# TPS60400.net
KiCad netlist of a schematic drawn in Altium Designer
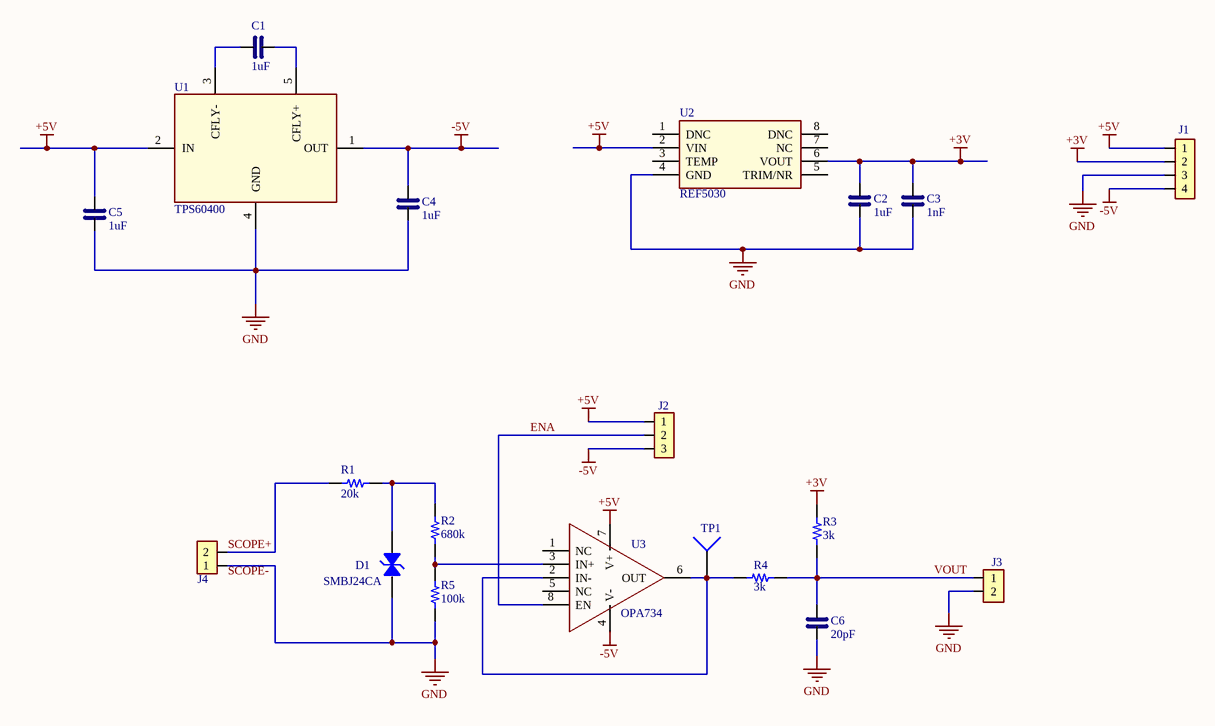
[diagram p0: TPS60400.SchDoc]

(export (version "E")
  (design (tool "Eeschema 10.0.6"))
  (components
    (comp (ref "C1")
      (value "1uF")
      (footprint "CAP 0805/2012")
      (libsource (lib "Capacitors") (part "CAP 0805/2012"))
    )
    (comp (ref "C2")
      (value "1uF")
      (footprint "CAP 0805/2012")
      (libsource (lib "Capacitors") (part "CAP 0805/2012"))
    )
    (comp (ref "C3")
      (value "1nF")
      (footprint "CAP 0805/2012")
      (libsource (lib "Capacitors") (part "CAP 0805/2012"))
    )
    (comp (ref "C4")
      (value "1uF")
      (footprint "CAP 0805/2012")
      (libsource (lib "Capacitors") (part "CAP 0805/2012"))
    )
    (comp (ref "C5")
      (value "1uF")
      (footprint "CAP 0805/2012")
      (libsource (lib "Capacitors") (part "CAP 0805/2012"))
    )
    (comp (ref "C6")
      (value "20pF")
      (footprint "CAP 0805/2012")
      (libsource (lib "Capacitors") (part "CAP 0805/2012"))
    )
    (comp (ref "D1")
      (value "SMBJ24CA")
      (footprint "ST DO214AA SMB")
      (description "DIODE SCHOTTKY 40V 2A DO214AA")
      (libsource (lib "Diodes") (part "ESD05V88D-LC"))
    )
    (comp (ref "J1")
      (value "Pin Header Male ( 4 pin )")
      (footprint "PIN HEADER MALE ( 4 PIN )")
      (libsource (lib "Connectors") (part "Pin Header Male ( 4 pin )"))
    )
    (comp (ref "J2")
      (value "Pin Header Male ( 3 pin )")
      (footprint "PIN HEADER male ( 3 pin )")
      (libsource (lib "Connectors") (part "Pin Header Male ( 3 pin )"))
    )
    (comp (ref "J3")
      (value "Pin Header Male ( 2 pin )")
      (footprint "PIN HEADER MALE ( 2 pin )")
      (libsource (lib "") (part "Pin Header Male ( 2 pin )_1"))
    )
    (comp (ref "J4")
      (value "Pin Header Male ( 2 pin )")
      (footprint "PIN HEADER MALE ( 2 pin )")
      (libsource (lib "Connectors") (part "Pin Header Male ( 2 pin )"))
    )
    (comp (ref "R1")
      (value "20k")
      (footprint "RES 0805/2012")
      (libsource (lib "Resistors") (part "RES 0805/2012 ( 1/8W )"))
    )
    (comp (ref "R2")
      (value "680k")
      (footprint "RES 0805/2012")
      (libsource (lib "Resistors") (part "RES 0805/2012 ( 1/8W )"))
    )
    (comp (ref "R3")
      (value "3k")
      (footprint "RES 0805/2012")
      (libsource (lib "Resistors") (part "RES 0805/2012 ( 1/8W )"))
    )
    (comp (ref "R4")
      (value "3k")
      (footprint "RES 0805/2012")
      (libsource (lib "Resistors") (part "RES 0805/2012 ( 1/8W )"))
    )
    (comp (ref "R5")
      (value "100k")
      (footprint "RES 0805/2012")
      (libsource (lib "Resistors") (part "RES 0805/2012 ( 1/8W )"))
    )
    (comp (ref "TP1")
      (value "Socket")
      (footprint "PIN1")
      (fields (field (name "PUBLISHER") "Altium Limited"))
      (libsource (lib "Miscellaneous Connectors") (part "Socket"))
    )
    (comp (ref "U1")
      (value "TPS60400")
      (footprint "SOT-23-5")
      (description "IC REG SWTCHD CAP INV 60MA SOT23")
      (libsource (lib "Integrated Circuits") (part "TPS60400"))
    )
    (comp (ref "U2")
      (value "REF5030")
      (footprint "SOIC-8 (150mil-3.9mm width)")
      (description "Series Voltage Reference IC ±0.1% 10mA")
      (libsource (lib "Integrated Circuits") (part "REF5030"))
    )
    (comp (ref "U3")
      (value "OPA734")
      (footprint "SOIC-8 (150mil-3.9mm width)")
      (description "IC OPAMP CHOPPER 1.6MHZ 8SOIC")
      (libsource (lib "Integrated Circuits") (part "OPA734"))
    )
  )
  (nets
    (net (code "1") (name "+3V") (class "Default")
      (node (ref "C2") (pin "2") (pinfunction "2_2") (pintype "passive"))
      (node (ref "C3") (pin "2") (pinfunction "2_2") (pintype "passive"))
      (node (ref "J1") (pin "2") (pinfunction "2_2") (pintype "power_in"))
      (node (ref "R3") (pin "1") (pinfunction "1_1") (pintype "passive"))
      (node (ref "U2") (pin "6") (pinfunction "VOUT_6") (pintype "passive"))
    )
    (net (code "2") (name "+5V") (class "Default")
      (node (ref "C5") (pin "2") (pinfunction "2_2") (pintype "passive"))
      (node (ref "J1") (pin "1") (pinfunction "1_1") (pintype "power_in"))
      (node (ref "J2") (pin "1") (pinfunction "1_1") (pintype "power_in"))
      (node (ref "U1") (pin "2") (pinfunction "IN_2") (pintype "power_in"))
      (node (ref "U2") (pin "2") (pinfunction "VIN_2") (pintype "passive"))
      (node (ref "U3") (pin "7") (pinfunction "V+_7") (pintype "passive"))
    )
    (net (code "3") (name "-5V") (class "Default")
      (node (ref "C4") (pin "2") (pinfunction "2_2") (pintype "passive"))
      (node (ref "J1") (pin "4") (pinfunction "4_4") (pintype "power_in"))
      (node (ref "J2") (pin "3") (pinfunction "3_3") (pintype "power_in"))
      (node (ref "U1") (pin "1") (pinfunction "OUT_1") (pintype "passive"))
      (node (ref "U3") (pin "4") (pinfunction "V-_4") (pintype "passive"))
    )
    (net (code "4") (name "/ENA") (class "Default")
      (node (ref "J2") (pin "2") (pinfunction "2_2") (pintype "power_in"))
      (node (ref "U3") (pin "8") (pinfunction "EN_8") (pintype "passive"))
    )
    (net (code "5") (name "/VOUT") (class "Default")
      (node (ref "C6") (pin "2") (pinfunction "2_2") (pintype "passive"))
      (node (ref "J3") (pin "1") (pinfunction "1_1") (pintype "power_in"))
      (node (ref "R3") (pin "2") (pinfunction "2_2") (pintype "passive"))
      (node (ref "R4") (pin "1") (pinfunction "1_1") (pintype "passive"))
    )
    (net (code "6") (name "GND") (class "Default")
      (node (ref "C2") (pin "1") (pinfunction "1_1") (pintype "passive"))
      (node (ref "C3") (pin "1") (pinfunction "1_1") (pintype "passive"))
      (node (ref "C4") (pin "1") (pinfunction "1_1") (pintype "passive"))
      (node (ref "C5") (pin "1") (pinfunction "1_1") (pintype "passive"))
      (node (ref "C6") (pin "1") (pinfunction "1_1") (pintype "passive"))
      (node (ref "D1") (pin "1") (pinfunction "1_1") (pintype "passive"))
      (node (ref "J1") (pin "3") (pinfunction "3_3") (pintype "power_in"))
      (node (ref "J3") (pin "2") (pinfunction "2_2") (pintype "power_in"))
      (node (ref "J4") (pin "1") (pinfunction "1_1") (pintype "power_in"))
      (node (ref "R5") (pin "1") (pinfunction "1_1") (pintype "passive"))
      (node (ref "U1") (pin "4") (pinfunction "GND_4") (pintype "passive"))
      (node (ref "U2") (pin "4") (pinfunction "GND_4") (pintype "passive"))
    )
    (net (code "7") (name "Net-(D1-Pad2)") (class "Default")
      (node (ref "D1") (pin "2") (pinfunction "2_2") (pintype "passive"))
      (node (ref "R1") (pin "1") (pinfunction "1_1") (pintype "passive"))
      (node (ref "R2") (pin "2") (pinfunction "2_2") (pintype "passive"))
    )
    (net (code "8") (name "Net-(J4-Pad2)") (class "Default")
      (node (ref "J4") (pin "2") (pinfunction "2_2") (pintype "power_in"))
      (node (ref "R1") (pin "2") (pinfunction "2_2") (pintype "passive"))
    )
    (net (code "9") (name "Net-(U1-CFLY+)") (class "Default")
      (node (ref "C1") (pin "1") (pinfunction "1_1") (pintype "passive"))
      (node (ref "U1") (pin "5") (pinfunction "CFLY+_5") (pintype "passive"))
    )
    (net (code "10") (name "Net-(U1-CFLY-)") (class "Default")
      (node (ref "C1") (pin "2") (pinfunction "2_2") (pintype "passive"))
      (node (ref "U1") (pin "3") (pinfunction "CFLY-_3") (pintype "passive"))
    )
    (net (code "11") (name "Net-(U3-IN+)") (class "Default")
      (node (ref "R2") (pin "1") (pinfunction "1_1") (pintype "passive"))
      (node (ref "R5") (pin "2") (pinfunction "2_2") (pintype "passive"))
      (node (ref "U3") (pin "3") (pinfunction "IN+_3") (pintype "passive"))
    )
    (net (code "12") (name "Net-(U3-IN-)") (class "Default")
      (node (ref "R4") (pin "2") (pinfunction "2_2") (pintype "passive"))
      (node (ref "TP1") (pin "1") (pinfunction "1_1") (pintype "passive"))
      (node (ref "U3") (pin "2") (pinfunction "IN-_2") (pintype "passive"))
      (node (ref "U3") (pin "6") (pinfunction "OUT_6") (pintype "passive"))
    )
    (net (code "13") (name "unconnected-(U2-DNC-Pad1)") (class "Default")
      (node (ref "U2") (pin "1") (pinfunction "DNC_1") (pintype "passive"))
    )
    (net (code "14") (name "unconnected-(U2-DNC-Pad8)") (class "Default")
      (node (ref "U2") (pin "8") (pinfunction "DNC_8") (pintype "passive"))
    )
    (net (code "15") (name "unconnected-(U2-NC-Pad7)") (class "Default")
      (node (ref "U2") (pin "7") (pinfunction "NC_7") (pintype "passive"))
    )
    (net (code "16") (name "unconnected-(U2-TEMP-Pad3)") (class "Default")
      (node (ref "U2") (pin "3") (pinfunction "TEMP_3") (pintype "passive"))
    )
    (net (code "17") (name "unconnected-(U2-TRIM{slash}NR-Pad5)") (class "Default")
      (node (ref "U2") (pin "5") (pinfunction "TRIM/NR_5") (pintype "passive"))
    )
    (net (code "18") (name "unconnected-(U3-NC-Pad1)") (class "Default")
      (node (ref "U3") (pin "1") (pinfunction "NC_1") (pintype "passive"))
    )
    (net (code "19") (name "unconnected-(U3-NC-Pad5)") (class "Default")
      (node (ref "U3") (pin "5") (pinfunction "NC_5") (pintype "passive"))
    )
  )
)
